# axiom_beta_plugin_module_TE0714_SATA_v0_.net
KiCad netlist of a schematic drawn in EAGLE
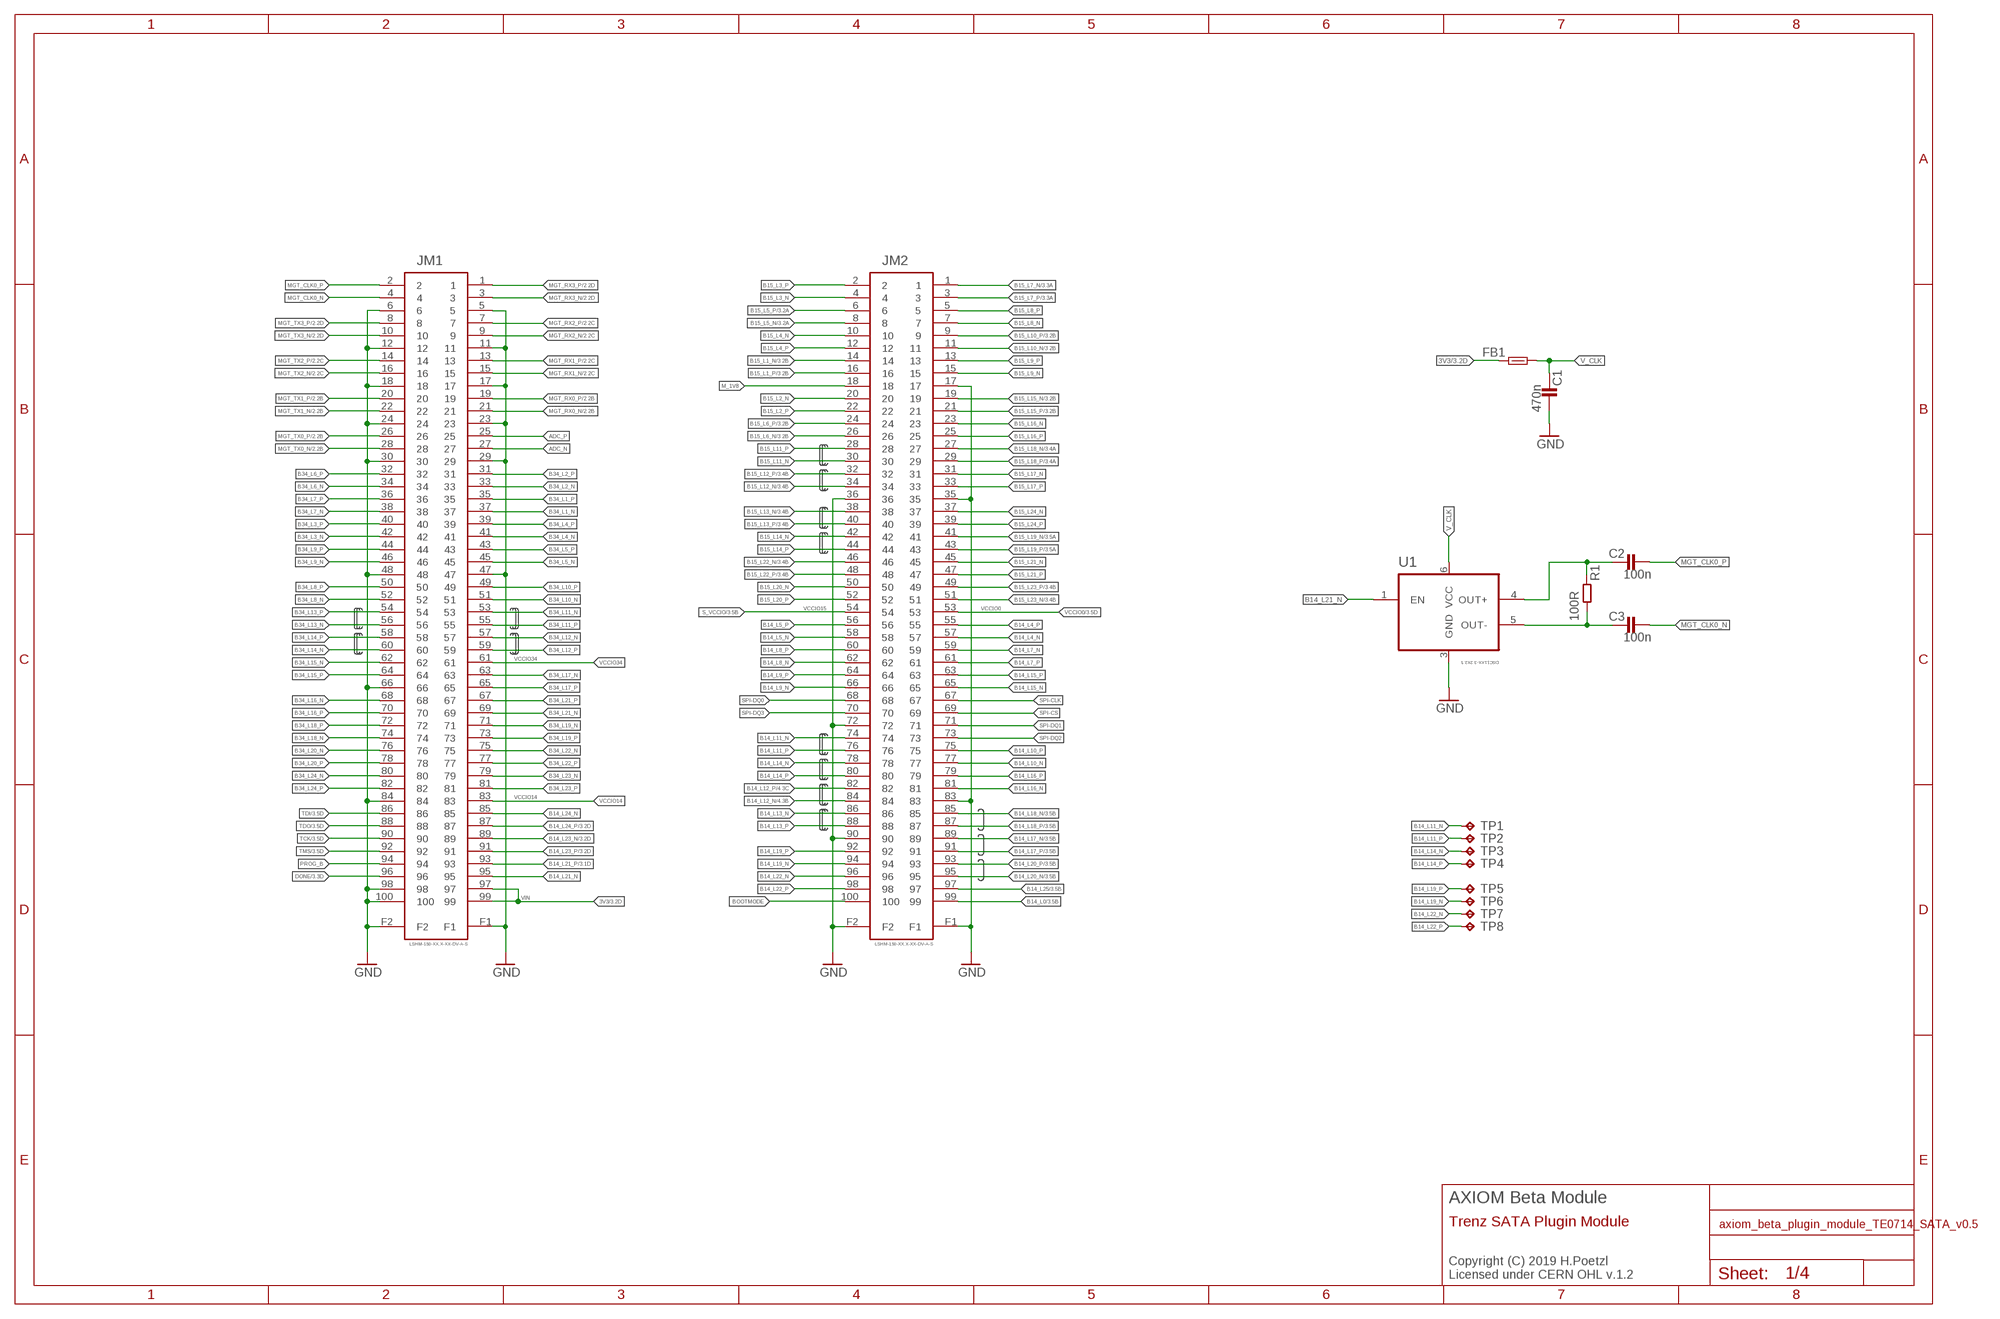
[diagram p0: schematic, sheet 1]
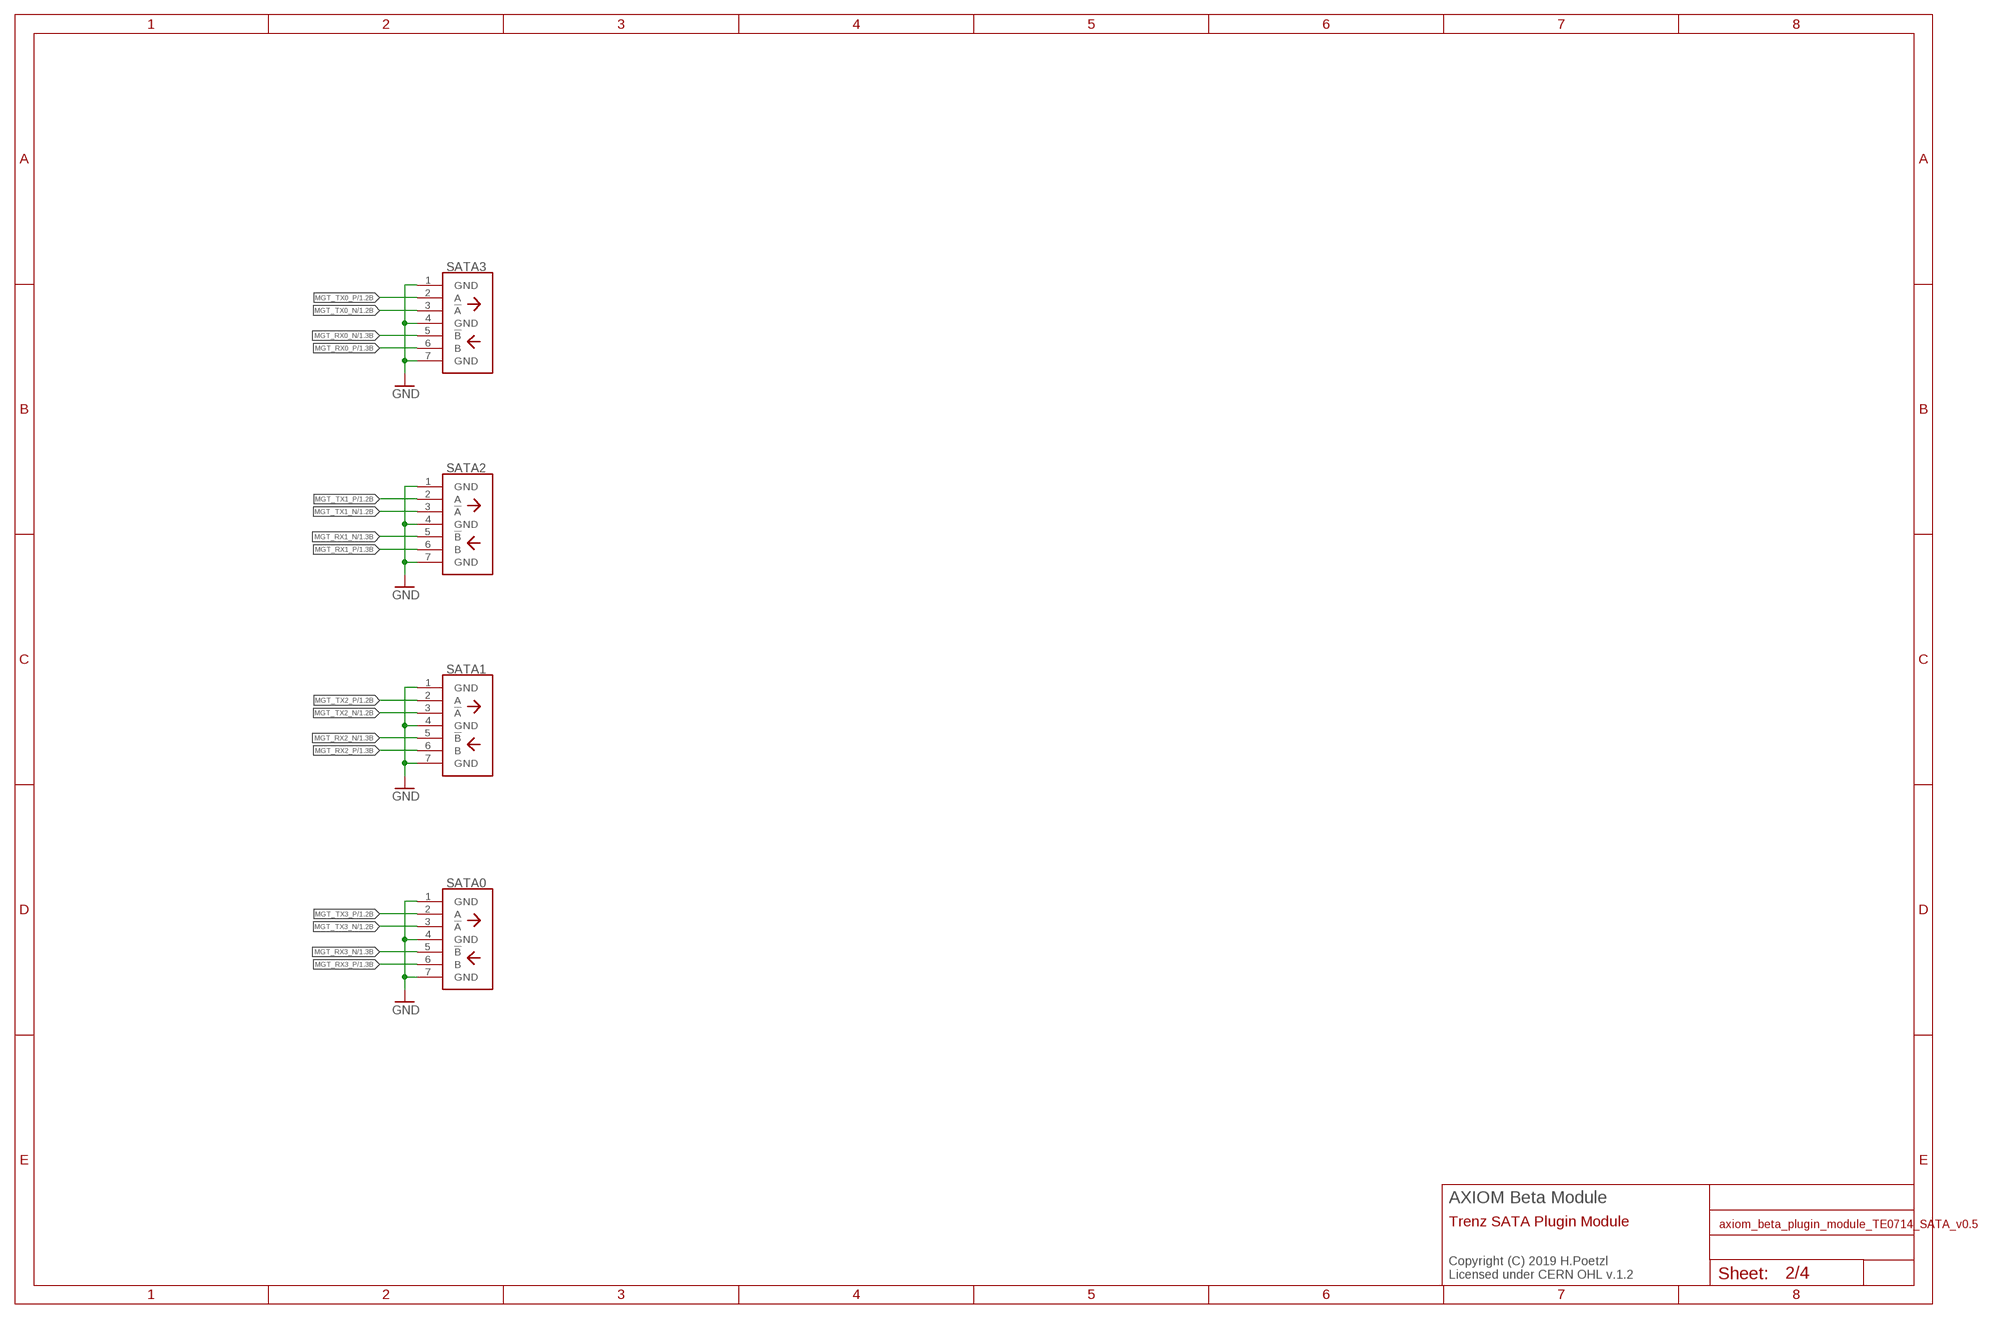
[diagram p1: schematic, sheet 2]
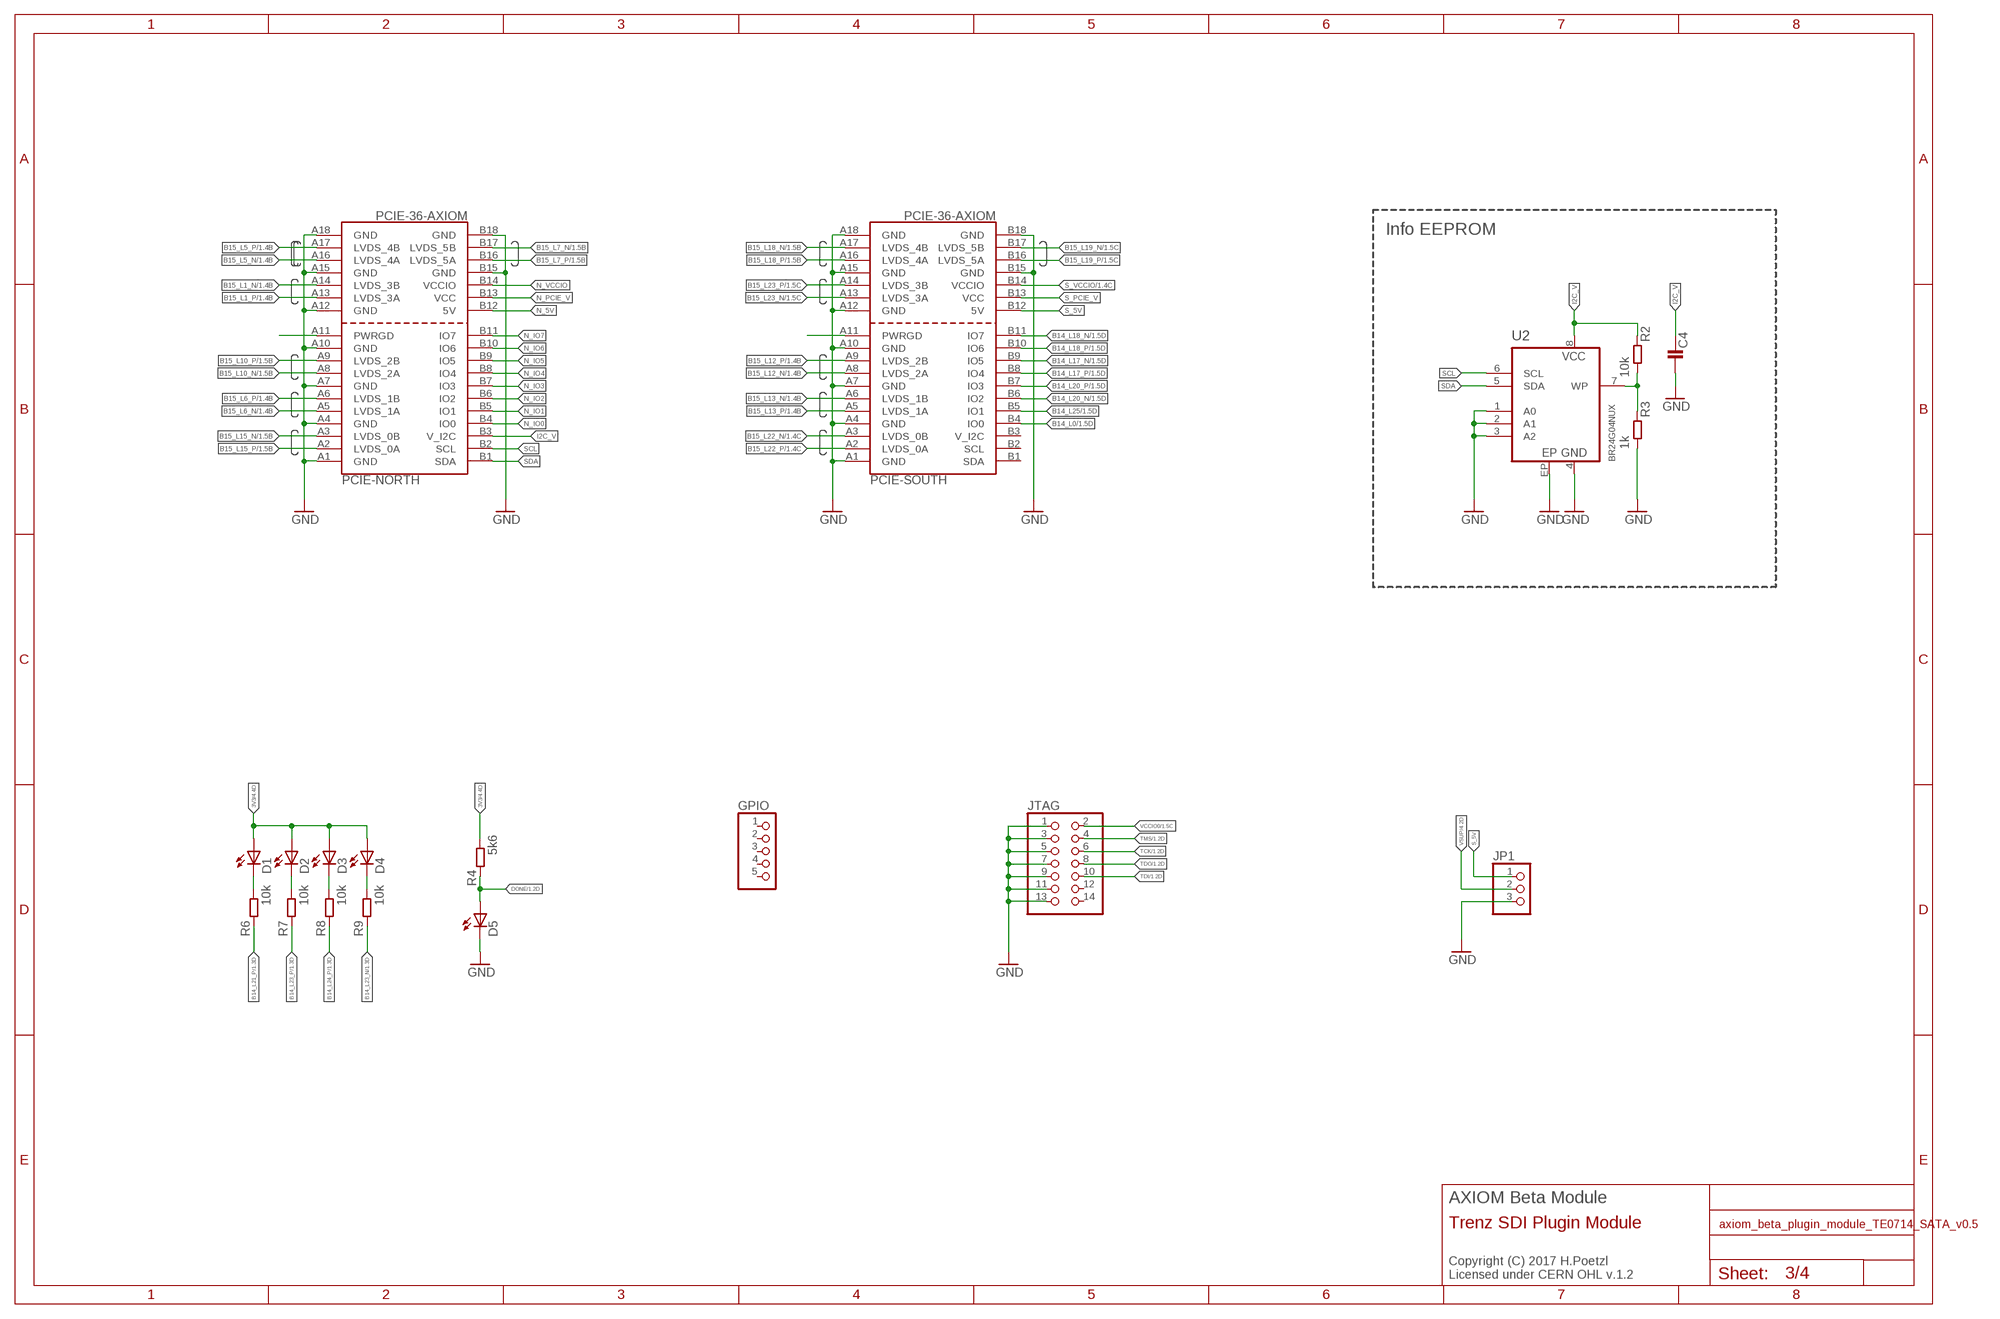
[diagram p2: schematic, sheet 3]
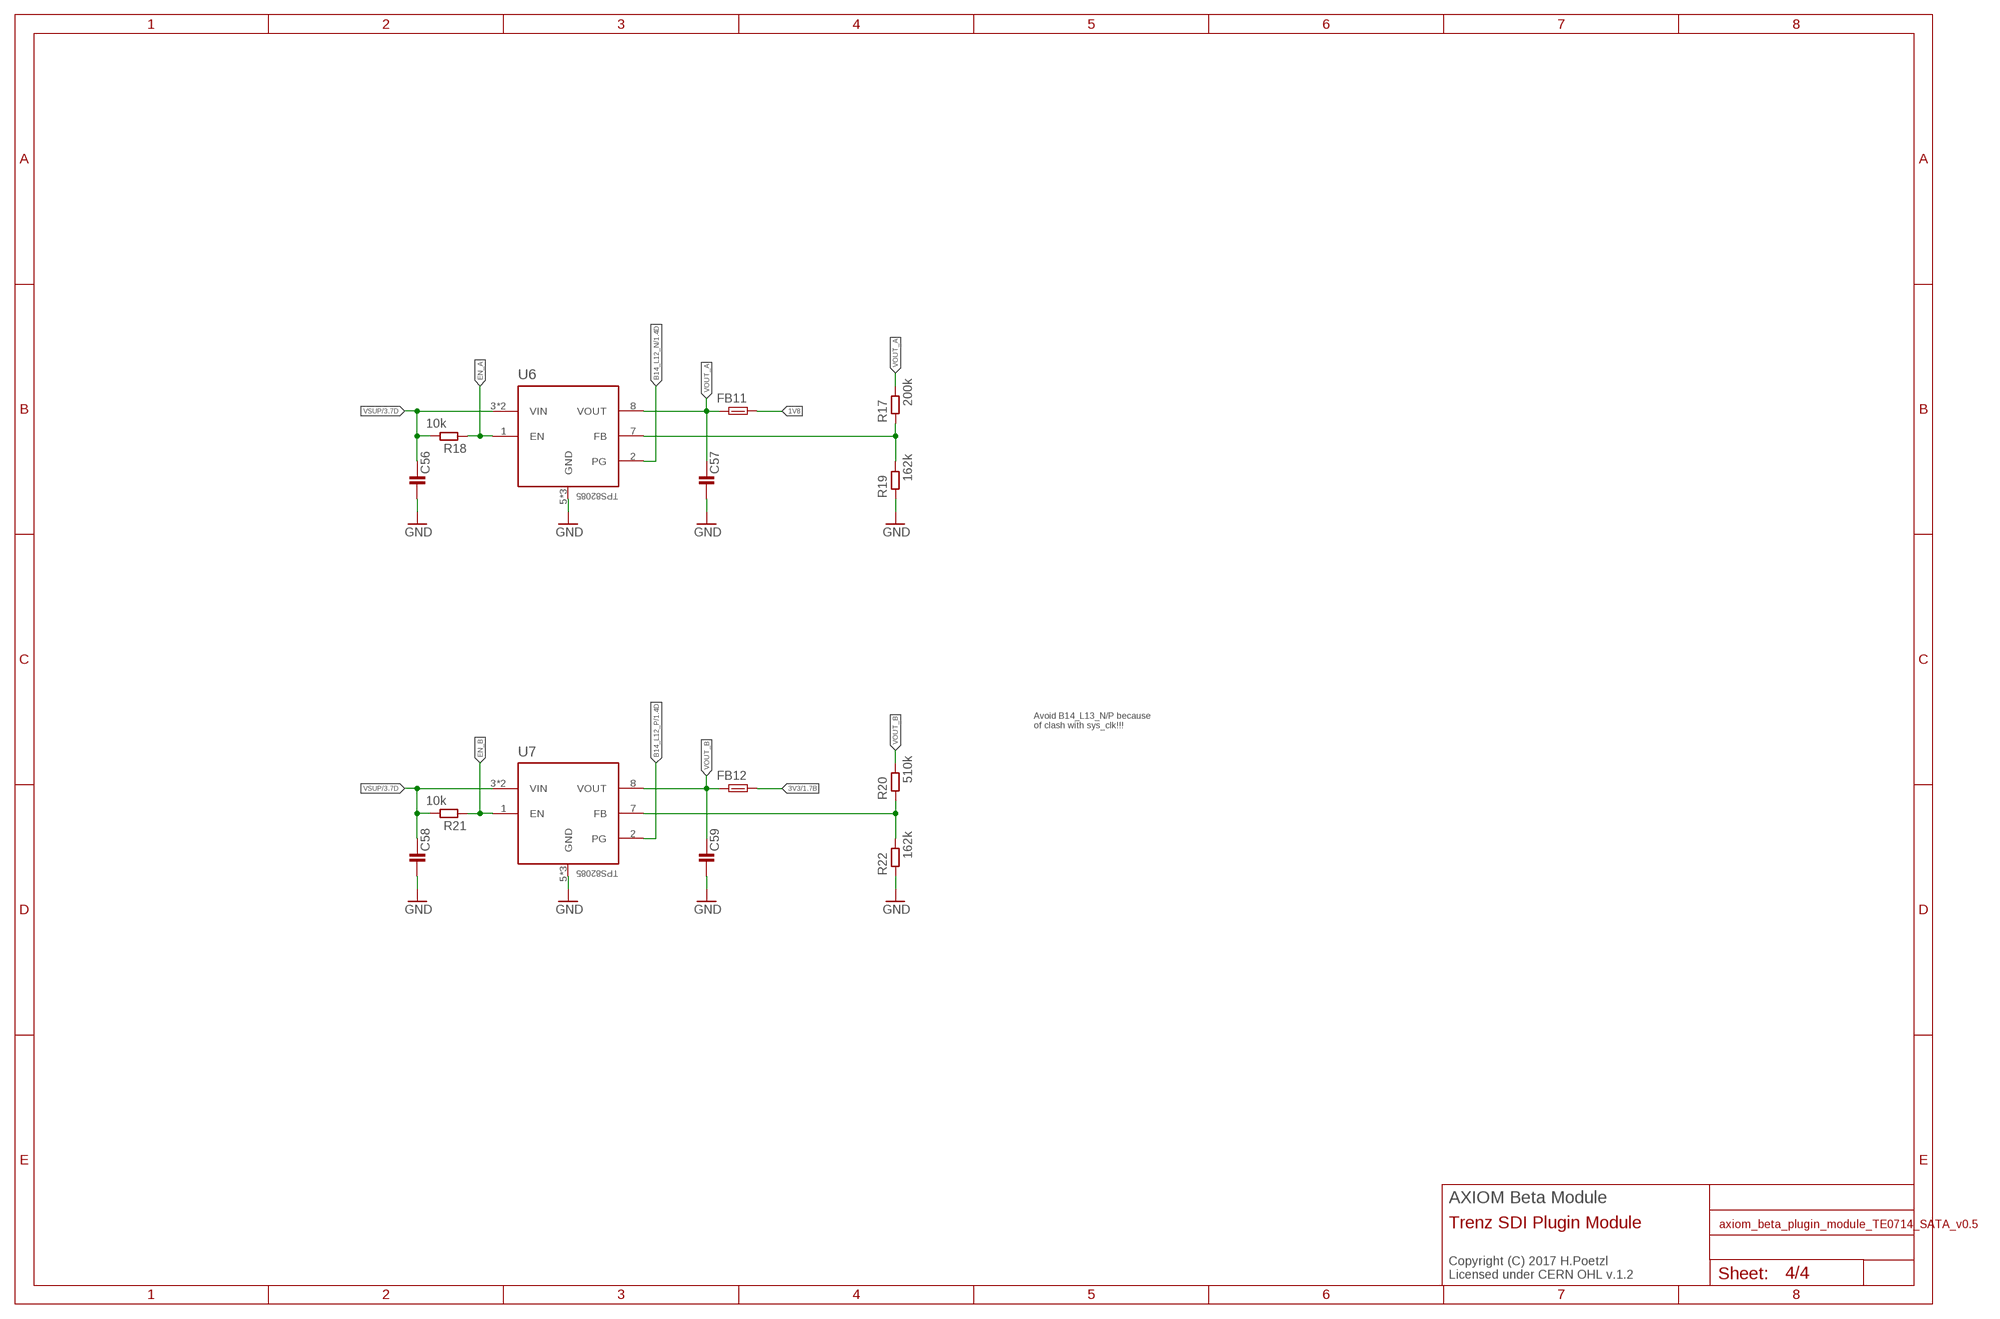
[diagram p3: schematic, sheet 4]

(export (version "E")
  (design (tool "Eeschema 10.0.6"))
  (components
    (comp (ref "C56")
      (value "C0603-C")
      (footprint "eagle-import:0603-C")
      (libsource (lib "eagle-import") (part "C0603-C"))
    )
    (comp (ref "C57")
      (value "C0603-C")
      (footprint "eagle-import:0603-C")
      (libsource (lib "eagle-import") (part "C0603-C"))
    )
    (comp (ref "C58")
      (value "C0603-C")
      (footprint "eagle-import:0603-C")
      (libsource (lib "eagle-import") (part "C0603-C"))
    )
    (comp (ref "C59")
      (value "C0603-C")
      (footprint "eagle-import:0603-C")
      (libsource (lib "eagle-import") (part "C0603-C"))
    )
    (comp (ref "FB11")
      (value "FB0603-C")
      (footprint "eagle-import:0603-C")
      (libsource (lib "eagle-import") (part "FB0603-C"))
    )
    (comp (ref "FB12")
      (value "FB0603-C")
      (footprint "eagle-import:0603-C")
      (libsource (lib "eagle-import") (part "FB0603-C"))
    )
    (comp (ref "R17")
      (value "200k")
      (footprint "eagle-import:0201-C")
      (libsource (lib "eagle-import") (part "R0201-C"))
    )
    (comp (ref "R18")
      (value "10k")
      (footprint "eagle-import:0201-C")
      (libsource (lib "eagle-import") (part "R0201-C"))
    )
    (comp (ref "R19")
      (value "162k")
      (footprint "eagle-import:0201-C")
      (libsource (lib "eagle-import") (part "R0201-C"))
    )
    (comp (ref "R20")
      (value "510k")
      (footprint "eagle-import:0201-C")
      (libsource (lib "eagle-import") (part "R0201-C"))
    )
    (comp (ref "R21")
      (value "10k")
      (footprint "eagle-import:0201-C")
      (libsource (lib "eagle-import") (part "R0201-C"))
    )
    (comp (ref "R22")
      (value "162k")
      (footprint "eagle-import:0201-C")
      (libsource (lib "eagle-import") (part "R0201-C"))
    )
    (comp (ref "U6")
      (value "TPS82085")
      (footprint "eagle-import:MICROSIP")
      (libsource (lib "eagle-import") (part "TPS82085"))
    )
    (comp (ref "U7")
      (value "TPS82085")
      (footprint "eagle-import:MICROSIP")
      (libsource (lib "eagle-import") (part "TPS82085"))
    )
    (comp (ref "C1")
      (value "470n")
      (footprint "eagle-import:0402-C")
      (libsource (lib "eagle-import") (part "C0402-C"))
    )
    (comp (ref "C2")
      (value "100n")
      (footprint "eagle-import:0201-C")
      (libsource (lib "eagle-import") (part "C0201-C"))
    )
    (comp (ref "C3")
      (value "100n")
      (footprint "eagle-import:0201-C")
      (libsource (lib "eagle-import") (part "C0201-C"))
    )
    (comp (ref "FB1")
      (value "FB0402-C")
      (footprint "eagle-import:0402-C")
      (libsource (lib "eagle-import") (part "FB0402-C"))
    )
    (comp (ref "JM1")
      (value "LSHM-150-XX.X-XX-DV-A-S")
      (footprint "eagle-import:LSHM-150-XX.X-XX-DV-A-S")
      (libsource (lib "eagle-import") (part "LSHM-150-XX.X-XX-DV-A-S"))
    )
    (comp (ref "JM2")
      (value "LSHM-150-XX.X-XX-DV-A-S")
      (footprint "eagle-import:LSHM-150-XX.X-XX-DV-A-S")
      (libsource (lib "eagle-import") (part "LSHM-150-XX.X-XX-DV-A-S"))
    )
    (comp (ref "R1")
      (value "100R")
      (footprint "eagle-import:0201-C")
      (libsource (lib "eagle-import") (part "R0201-C"))
    )
    (comp (ref "TP1")
      (value "TPTP08R")
      (footprint "eagle-import:TP08R")
      (libsource (lib "eagle-import") (part "TPTP08R"))
    )
    (comp (ref "TP2")
      (value "TPTP08R")
      (footprint "eagle-import:TP08R")
      (libsource (lib "eagle-import") (part "TPTP08R"))
    )
    (comp (ref "TP3")
      (value "TPTP08R")
      (footprint "eagle-import:TP08R")
      (libsource (lib "eagle-import") (part "TPTP08R"))
    )
    (comp (ref "TP4")
      (value "TPTP08R")
      (footprint "eagle-import:TP08R")
      (libsource (lib "eagle-import") (part "TPTP08R"))
    )
    (comp (ref "TP5")
      (value "TPTP10R")
      (footprint "eagle-import:TP10R")
      (libsource (lib "eagle-import") (part "TPTP10R"))
    )
    (comp (ref "TP6")
      (value "TPTP10R")
      (footprint "eagle-import:TP10R")
      (libsource (lib "eagle-import") (part "TPTP10R"))
    )
    (comp (ref "TP7")
      (value "TPTP10R")
      (footprint "eagle-import:TP10R")
      (libsource (lib "eagle-import") (part "TPTP10R"))
    )
    (comp (ref "TP8")
      (value "TPTP10R")
      (footprint "eagle-import:TP10R")
      (libsource (lib "eagle-import") (part "TPTP10R"))
    )
    (comp (ref "U1")
      (value "DSC11XX-3.2X2.5")
      (footprint "eagle-import:3.2X2.5")
      (libsource (lib "eagle-import") (part "DSC11XX-3.2X2.5"))
    )
    (comp (ref "SATA0")
      (value "SATA7-VERT")
      (footprint "eagle-import:SATA7-VERT")
      (libsource (lib "eagle-import") (part "SATA7-VERT"))
    )
    (comp (ref "SATA1")
      (value "SATA7-VERT")
      (footprint "eagle-import:SATA7-VERT")
      (libsource (lib "eagle-import") (part "SATA7-VERT"))
    )
    (comp (ref "SATA2")
      (value "SATA7-VERT")
      (footprint "eagle-import:SATA7-VERT")
      (libsource (lib "eagle-import") (part "SATA7-VERT"))
    )
    (comp (ref "SATA3")
      (value "SATA7-VERT")
      (footprint "eagle-import:SATA7-VERT")
      (libsource (lib "eagle-import") (part "SATA7-VERT"))
    )
    (comp (ref "C4")
      (value "C0402-B")
      (footprint "eagle-import:0402-B")
      (libsource (lib "eagle-import") (part "C0402-B"))
    )
    (comp (ref "D1")
      (value "LED")
      (footprint "eagle-import:CHIPLED_0603")
      (libsource (lib "eagle-import") (part "LED"))
    )
    (comp (ref "D2")
      (value "LED")
      (footprint "eagle-import:CHIPLED_0603")
      (libsource (lib "eagle-import") (part "LED"))
    )
    (comp (ref "D3")
      (value "LED")
      (footprint "eagle-import:CHIPLED_0603")
      (libsource (lib "eagle-import") (part "LED"))
    )
    (comp (ref "D4")
      (value "LED")
      (footprint "eagle-import:CHIPLED_0603")
      (libsource (lib "eagle-import") (part "LED"))
    )
    (comp (ref "D5")
      (value "LED")
      (footprint "eagle-import:CHIPLED_0603")
      (libsource (lib "eagle-import") (part "LED"))
    )
    (comp (ref "GPIO")
      (value "PINHD-1X05_2.00")
      (footprint "eagle-import:1X05M")
      (libsource (lib "eagle-import") (part "PINHD-1X05_2.00"))
    )
    (comp (ref "JP1")
      (value "PINHD-1X03_2.54-90°-S")
      (footprint "eagle-import:1X03_90-S")
      (libsource (lib "eagle-import") (part "PINHD-1X03_2.54-90°-S"))
    )
    (comp (ref "JTAG")
      (value "PINHD-2X07_2.00")
      (footprint "eagle-import:2X07M")
      (libsource (lib "eagle-import") (part "PINHD-2X07_2.00"))
    )
    (comp (ref "PCIE-NORTH")
      (value "PCIE-36-AXIOM")
      (footprint "eagle-import:PCIE-36-AXIOM")
      (libsource (lib "eagle-import") (part "PCIE-36-AXIOM"))
    )
    (comp (ref "PCIE-SOUTH")
      (value "PCIE-36-AXIOM")
      (footprint "eagle-import:PCIE-36-AXIOM")
      (libsource (lib "eagle-import") (part "PCIE-36-AXIOM"))
    )
    (comp (ref "R2")
      (value "10k")
      (footprint "eagle-import:0402-B")
      (libsource (lib "eagle-import") (part "R0402-B"))
    )
    (comp (ref "R3")
      (value "1k")
      (footprint "eagle-import:0402-B")
      (libsource (lib "eagle-import") (part "R0402-B"))
    )
    (comp (ref "R4")
      (value "5k6")
      (footprint "eagle-import:0402-C")
      (libsource (lib "eagle-import") (part "R0402-C"))
    )
    (comp (ref "R6")
      (value "10k")
      (footprint "eagle-import:0402-C")
      (libsource (lib "eagle-import") (part "R0402-C"))
    )
    (comp (ref "R7")
      (value "10k")
      (footprint "eagle-import:0402-C")
      (libsource (lib "eagle-import") (part "R0402-C"))
    )
    (comp (ref "R8")
      (value "10k")
      (footprint "eagle-import:0402-C")
      (libsource (lib "eagle-import") (part "R0402-C"))
    )
    (comp (ref "R9")
      (value "10k")
      (footprint "eagle-import:0402-C")
      (libsource (lib "eagle-import") (part "R0402-C"))
    )
    (comp (ref "U2")
      (value "BR24G04NUX")
      (footprint "eagle-import:DFN200X300X100-9N")
      (libsource (lib "eagle-import") (part "BR24G04NUX"))
    )
  )
  (nets
    (net (code "1") (name "1V8") (class "Default")
      (node (ref "FB11") (pin "2") (pinfunction "2_2") (pintype "passive"))
    )
    (net (code "2") (name "3V3") (class "Default")
      (node (ref "D1") (pin "A") (pinfunction "A_A") (pintype "passive"))
      (node (ref "D2") (pin "A") (pinfunction "A_A") (pintype "passive"))
      (node (ref "D3") (pin "A") (pinfunction "A_A") (pintype "passive"))
      (node (ref "D4") (pin "A") (pinfunction "A_A") (pintype "passive"))
      (node (ref "FB1") (pin "1") (pinfunction "1_1") (pintype "passive"))
      (node (ref "FB12") (pin "2") (pinfunction "2_2") (pintype "passive"))
      (node (ref "JM1") (pin "97") (pinfunction "97_97") (pintype "bidirectional"))
      (node (ref "JM1") (pin "99") (pinfunction "99_99") (pintype "bidirectional"))
      (node (ref "R4") (pin "2") (pinfunction "2_2") (pintype "passive"))
    )
    (net (code "3") (name "ADC_N") (class "Default")
      (node (ref "JM1") (pin "27") (pinfunction "27_27") (pintype "bidirectional"))
    )
    (net (code "4") (name "ADC_P") (class "Default")
      (node (ref "JM1") (pin "25") (pinfunction "25_25") (pintype "bidirectional"))
    )
    (net (code "5") (name "B14_L0") (class "Default")
      (node (ref "JM2") (pin "99") (pinfunction "99_99") (pintype "bidirectional"))
      (node (ref "PCIE-SOUTH") (pin "B4") (pinfunction "IO0_B4") (pintype "passive"))
    )
    (net (code "6") (name "B14_L4_N") (class "Default")
      (node (ref "JM2") (pin "57") (pinfunction "57_57") (pintype "bidirectional"))
    )
    (net (code "7") (name "B14_L4_P") (class "Default")
      (node (ref "JM2") (pin "55") (pinfunction "55_55") (pintype "bidirectional"))
    )
    (net (code "8") (name "B14_L5_N") (class "Default")
      (node (ref "JM2") (pin "58") (pinfunction "58_58") (pintype "bidirectional"))
    )
    (net (code "9") (name "B14_L5_P") (class "Default")
      (node (ref "JM2") (pin "56") (pinfunction "56_56") (pintype "bidirectional"))
    )
    (net (code "10") (name "B14_L7_N") (class "Default")
      (node (ref "JM2") (pin "59") (pinfunction "59_59") (pintype "bidirectional"))
    )
    (net (code "11") (name "B14_L7_P") (class "Default")
      (node (ref "JM2") (pin "61") (pinfunction "61_61") (pintype "bidirectional"))
    )
    (net (code "12") (name "B14_L8_N") (class "Default")
      (node (ref "JM2") (pin "62") (pinfunction "62_62") (pintype "bidirectional"))
    )
    (net (code "13") (name "B14_L8_P") (class "Default")
      (node (ref "JM2") (pin "60") (pinfunction "60_60") (pintype "bidirectional"))
    )
    (net (code "14") (name "B14_L9_N") (class "Default")
      (node (ref "JM2") (pin "66") (pinfunction "66_66") (pintype "bidirectional"))
    )
    (net (code "15") (name "B14_L9_P") (class "Default")
      (node (ref "JM2") (pin "64") (pinfunction "64_64") (pintype "bidirectional"))
    )
    (net (code "16") (name "B14_L10_N") (class "Default")
      (node (ref "JM2") (pin "77") (pinfunction "77_77") (pintype "bidirectional"))
    )
    (net (code "17") (name "B14_L10_P") (class "Default")
      (node (ref "JM2") (pin "75") (pinfunction "75_75") (pintype "bidirectional"))
    )
    (net (code "18") (name "B14_L11_N") (class "Default")
      (node (ref "JM2") (pin "74") (pinfunction "74_74") (pintype "bidirectional"))
      (node (ref "TP1") (pin "TP") (pinfunction "TP_TP") (pintype "input"))
    )
    (net (code "19") (name "B14_L11_P") (class "Default")
      (node (ref "JM2") (pin "76") (pinfunction "76_76") (pintype "bidirectional"))
      (node (ref "TP2") (pin "TP") (pinfunction "TP_TP") (pintype "input"))
    )
    (net (code "20") (name "B14_L12_N") (class "Default")
      (node (ref "JM2") (pin "84") (pinfunction "84_84") (pintype "bidirectional"))
      (node (ref "U6") (pin "2") (pinfunction "PG_2") (pintype "power_in"))
    )
    (net (code "21") (name "B14_L12_P") (class "Default")
      (node (ref "JM2") (pin "82") (pinfunction "82_82") (pintype "bidirectional"))
      (node (ref "U7") (pin "2") (pinfunction "PG_2") (pintype "power_in"))
    )
    (net (code "22") (name "B14_L13_N") (class "Default")
      (node (ref "JM2") (pin "86") (pinfunction "86_86") (pintype "bidirectional"))
    )
    (net (code "23") (name "B14_L13_P") (class "Default")
      (node (ref "JM2") (pin "88") (pinfunction "88_88") (pintype "bidirectional"))
    )
    (net (code "24") (name "B14_L14_N") (class "Default")
      (node (ref "JM2") (pin "78") (pinfunction "78_78") (pintype "bidirectional"))
      (node (ref "TP3") (pin "TP") (pinfunction "TP_TP") (pintype "input"))
    )
    (net (code "25") (name "B14_L14_P") (class "Default")
      (node (ref "JM2") (pin "80") (pinfunction "80_80") (pintype "bidirectional"))
      (node (ref "TP4") (pin "TP") (pinfunction "TP_TP") (pintype "input"))
    )
    (net (code "26") (name "B14_L15_N") (class "Default")
      (node (ref "JM2") (pin "65") (pinfunction "65_65") (pintype "bidirectional"))
    )
    (net (code "27") (name "B14_L15_P") (class "Default")
      (node (ref "JM2") (pin "63") (pinfunction "63_63") (pintype "bidirectional"))
    )
    (net (code "28") (name "B14_L16_N") (class "Default")
      (node (ref "JM2") (pin "81") (pinfunction "81_81") (pintype "bidirectional"))
    )
    (net (code "29") (name "B14_L16_P") (class "Default")
      (node (ref "JM2") (pin "79") (pinfunction "79_79") (pintype "bidirectional"))
    )
    (net (code "30") (name "B14_L17_N") (class "Default")
      (node (ref "JM2") (pin "89") (pinfunction "89_89") (pintype "bidirectional"))
      (node (ref "PCIE-SOUTH") (pin "B9") (pinfunction "IO5_B9") (pintype "passive"))
    )
    (net (code "31") (name "B14_L17_P") (class "Default")
      (node (ref "JM2") (pin "91") (pinfunction "91_91") (pintype "bidirectional"))
      (node (ref "PCIE-SOUTH") (pin "B8") (pinfunction "IO4_B8") (pintype "passive"))
    )
    (net (code "32") (name "B14_L18_N") (class "Default")
      (node (ref "JM2") (pin "85") (pinfunction "85_85") (pintype "bidirectional"))
      (node (ref "PCIE-SOUTH") (pin "B11") (pinfunction "IO7_B11") (pintype "passive"))
    )
    (net (code "33") (name "B14_L18_P") (class "Default")
      (node (ref "JM2") (pin "87") (pinfunction "87_87") (pintype "bidirectional"))
      (node (ref "PCIE-SOUTH") (pin "B10") (pinfunction "IO6_B10") (pintype "passive"))
    )
    (net (code "34") (name "B14_L19_N") (class "Default")
      (node (ref "JM2") (pin "94") (pinfunction "94_94") (pintype "bidirectional"))
      (node (ref "TP6") (pin "TP") (pinfunction "TP_TP") (pintype "input"))
    )
    (net (code "35") (name "B14_L19_P") (class "Default")
      (node (ref "JM2") (pin "92") (pinfunction "92_92") (pintype "bidirectional"))
      (node (ref "TP5") (pin "TP") (pinfunction "TP_TP") (pintype "input"))
    )
    (net (code "36") (name "B14_L20_N") (class "Default")
      (node (ref "JM2") (pin "95") (pinfunction "95_95") (pintype "bidirectional"))
      (node (ref "PCIE-SOUTH") (pin "B6") (pinfunction "IO2_B6") (pintype "passive"))
    )
    (net (code "37") (name "B14_L20_P") (class "Default")
      (node (ref "JM2") (pin "93") (pinfunction "93_93") (pintype "bidirectional"))
      (node (ref "PCIE-SOUTH") (pin "B7") (pinfunction "IO3_B7") (pintype "passive"))
    )
    (net (code "38") (name "B14_L21_N") (class "Default")
      (node (ref "JM1") (pin "95") (pinfunction "95_95") (pintype "bidirectional"))
      (node (ref "U1") (pin "1") (pinfunction "EN_1") (pintype "input"))
    )
    (net (code "39") (name "B14_L21_P") (class "Default")
      (node (ref "JM1") (pin "93") (pinfunction "93_93") (pintype "bidirectional"))
      (node (ref "R6") (pin "1") (pinfunction "1_1") (pintype "passive"))
    )
    (net (code "40") (name "B14_L22_N") (class "Default")
      (node (ref "JM2") (pin "96") (pinfunction "96_96") (pintype "bidirectional"))
      (node (ref "TP7") (pin "TP") (pinfunction "TP_TP") (pintype "input"))
    )
    (net (code "41") (name "B14_L22_P") (class "Default")
      (node (ref "JM2") (pin "98") (pinfunction "98_98") (pintype "bidirectional"))
      (node (ref "TP8") (pin "TP") (pinfunction "TP_TP") (pintype "input"))
    )
    (net (code "42") (name "B14_L23_N") (class "Default")
      (node (ref "JM1") (pin "89") (pinfunction "89_89") (pintype "bidirectional"))
      (node (ref "R9") (pin "1") (pinfunction "1_1") (pintype "passive"))
    )
    (net (code "43") (name "B14_L23_P") (class "Default")
      (node (ref "JM1") (pin "91") (pinfunction "91_91") (pintype "bidirectional"))
      (node (ref "R7") (pin "1") (pinfunction "1_1") (pintype "passive"))
    )
    (net (code "44") (name "B14_L24_N") (class "Default")
      (node (ref "JM1") (pin "85") (pinfunction "85_85") (pintype "bidirectional"))
    )
    (net (code "45") (name "B14_L24_P") (class "Default")
      (node (ref "JM1") (pin "87") (pinfunction "87_87") (pintype "bidirectional"))
      (node (ref "R8") (pin "1") (pinfunction "1_1") (pintype "passive"))
    )
    (net (code "46") (name "B14_L25") (class "Default")
      (node (ref "JM2") (pin "97") (pinfunction "97_97") (pintype "bidirectional"))
      (node (ref "PCIE-SOUTH") (pin "B5") (pinfunction "IO1_B5") (pintype "passive"))
    )
    (net (code "47") (name "B15_L1_N") (class "Default")
      (node (ref "JM2") (pin "14") (pinfunction "14_14") (pintype "bidirectional"))
      (node (ref "PCIE-NORTH") (pin "A14") (pinfunction "LVDS_3B_A14") (pintype "passive"))
    )
    (net (code "48") (name "B15_L1_P") (class "Default")
      (node (ref "JM2") (pin "16") (pinfunction "16_16") (pintype "bidirectional"))
      (node (ref "PCIE-NORTH") (pin "A13") (pinfunction "LVDS_3A_A13") (pintype "passive"))
    )
    (net (code "49") (name "B15_L2_N") (class "Default")
      (node (ref "JM2") (pin "20") (pinfunction "20_20") (pintype "bidirectional"))
    )
    (net (code "50") (name "B15_L2_P") (class "Default")
      (node (ref "JM2") (pin "22") (pinfunction "22_22") (pintype "bidirectional"))
    )
    (net (code "51") (name "B15_L3_N") (class "Default")
      (node (ref "JM2") (pin "4") (pinfunction "4_4") (pintype "bidirectional"))
    )
    (net (code "52") (name "B15_L3_P") (class "Default")
      (node (ref "JM2") (pin "2") (pinfunction "2_2") (pintype "bidirectional"))
    )
    (net (code "53") (name "B15_L4_N") (class "Default")
      (node (ref "JM2") (pin "10") (pinfunction "10_10") (pintype "bidirectional"))
    )
    (net (code "54") (name "B15_L4_P") (class "Default")
      (node (ref "JM2") (pin "12") (pinfunction "12_12") (pintype "bidirectional"))
    )
    (net (code "55") (name "B15_L5_N") (class "Default")
      (node (ref "JM2") (pin "8") (pinfunction "8_8") (pintype "bidirectional"))
      (node (ref "PCIE-NORTH") (pin "A16") (pinfunction "LVDS_4A_A16") (pintype "passive"))
    )
    (net (code "56") (name "B15_L5_P") (class "Default")
      (node (ref "JM2") (pin "6") (pinfunction "6_6") (pintype "bidirectional"))
      (node (ref "PCIE-NORTH") (pin "A17") (pinfunction "LVDS_4B_A17") (pintype "passive"))
    )
    (net (code "57") (name "B15_L6_N") (class "Default")
      (node (ref "JM2") (pin "26") (pinfunction "26_26") (pintype "bidirectional"))
      (node (ref "PCIE-NORTH") (pin "A5") (pinfunction "LVDS_1A_A5") (pintype "passive"))
    )
    (net (code "58") (name "B15_L6_P") (class "Default")
      (node (ref "JM2") (pin "24") (pinfunction "24_24") (pintype "bidirectional"))
      (node (ref "PCIE-NORTH") (pin "A6") (pinfunction "LVDS_1B_A6") (pintype "passive"))
    )
    (net (code "59") (name "B15_L7_N") (class "Default")
      (node (ref "JM2") (pin "1") (pinfunction "1_1") (pintype "bidirectional"))
      (node (ref "PCIE-NORTH") (pin "B17") (pinfunction "LVDS_5B_B17") (pintype "passive"))
    )
    (net (code "60") (name "B15_L7_P") (class "Default")
      (node (ref "JM2") (pin "3") (pinfunction "3_3") (pintype "bidirectional"))
      (node (ref "PCIE-NORTH") (pin "B16") (pinfunction "LVDS_5A_B16") (pintype "passive"))
    )
    (net (code "61") (name "B15_L8_N") (class "Default")
      (node (ref "JM2") (pin "7") (pinfunction "7_7") (pintype "bidirectional"))
    )
    (net (code "62") (name "B15_L8_P") (class "Default")
      (node (ref "JM2") (pin "5") (pinfunction "5_5") (pintype "bidirectional"))
    )
    (net (code "63") (name "B15_L9_N") (class "Default")
      (node (ref "JM2") (pin "15") (pinfunction "15_15") (pintype "bidirectional"))
    )
    (net (code "64") (name "B15_L9_P") (class "Default")
      (node (ref "JM2") (pin "13") (pinfunction "13_13") (pintype "bidirectional"))
    )
    (net (code "65") (name "B15_L10_N") (class "Default")
      (node (ref "JM2") (pin "11") (pinfunction "11_11") (pintype "bidirectional"))
      (node (ref "PCIE-NORTH") (pin "A8") (pinfunction "LVDS_2A_A8") (pintype "passive"))
    )
    (net (code "66") (name "B15_L10_P") (class "Default")
      (node (ref "JM2") (pin "9") (pinfunction "9_9") (pintype "bidirectional"))
      (node (ref "PCIE-NORTH") (pin "A9") (pinfunction "LVDS_2B_A9") (pintype "passive"))
    )
    (net (code "67") (name "B15_L11_N") (class "Default")
      (node (ref "JM2") (pin "30") (pinfunction "30_30") (pintype "bidirectional"))
    )
    (net (code "68") (name "B15_L11_P") (class "Default")
      (node (ref "JM2") (pin "28") (pinfunction "28_28") (pintype "bidirectional"))
    )
    (net (code "69") (name "B15_L12_N") (class "Default")
      (node (ref "JM2") (pin "34") (pinfunction "34_34") (pintype "bidirectional"))
      (node (ref "PCIE-SOUTH") (pin "A8") (pinfunction "LVDS_2A_A8") (pintype "passive"))
    )
    (net (code "70") (name "B15_L12_P") (class "Default")
      (node (ref "JM2") (pin "32") (pinfunction "32_32") (pintype "bidirectional"))
      (node (ref "PCIE-SOUTH") (pin "A9") (pinfunction "LVDS_2B_A9") (pintype "passive"))
    )
    (net (code "71") (name "B15_L13_N") (class "Default")
      (node (ref "JM2") (pin "38") (pinfunction "38_38") (pintype "bidirectional"))
      (node (ref "PCIE-SOUTH") (pin "A6") (pinfunction "LVDS_1B_A6") (pintype "passive"))
    )
    (net (code "72") (name "B15_L13_P") (class "Default")
      (node (ref "JM2") (pin "40") (pinfunction "40_40") (pintype "bidirectional"))
      (node (ref "PCIE-SOUTH") (pin "A5") (pinfunction "LVDS_1A_A5") (pintype "passive"))
    )
    (net (code "73") (name "B15_L14_N") (class "Default")
      (node (ref "JM2") (pin "42") (pinfunction "42_42") (pintype "bidirectional"))
    )
    (net (code "74") (name "B15_L14_P") (class "Default")
      (node (ref "JM2") (pin "44") (pinfunction "44_44") (pintype "bidirectional"))
    )
    (net (code "75") (name "B15_L15_N") (class "Default")
      (node (ref "JM2") (pin "19") (pinfunction "19_19") (pintype "bidirectional"))
      (node (ref "PCIE-NORTH") (pin "A3") (pinfunction "LVDS_0B_A3") (pintype "passive"))
    )
    (net (code "76") (name "B15_L15_P") (class "Default")
      (node (ref "JM2") (pin "21") (pinfunction "21_21") (pintype "bidirectional"))
      (node (ref "PCIE-NORTH") (pin "A2") (pinfunction "LVDS_0A_A2") (pintype "passive"))
    )
    (net (code "77") (name "B15_L16_N") (class "Default")
      (node (ref "JM2") (pin "23") (pinfunction "23_23") (pintype "bidirectional"))
    )
    (net (code "78") (name "B15_L16_P") (class "Default")
      (node (ref "JM2") (pin "25") (pinfunction "25_25") (pintype "bidirectional"))
    )
    (net (code "79") (name "B15_L17_N") (class "Default")
      (node (ref "JM2") (pin "31") (pinfunction "31_31") (pintype "bidirectional"))
    )
    (net (code "80") (name "B15_L17_P") (class "Default")
      (node (ref "JM2") (pin "33") (pinfunction "33_33") (pintype "bidirectional"))
    )
    (net (code "81") (name "B15_L18_N") (class "Default")
      (node (ref "JM2") (pin "27") (pinfunction "27_27") (pintype "bidirectional"))
      (node (ref "PCIE-SOUTH") (pin "A17") (pinfunction "LVDS_4B_A17") (pintype "passive"))
    )
    (net (code "82") (name "B15_L18_P") (class "Default")
      (node (ref "JM2") (pin "29") (pinfunction "29_29") (pintype "bidirectional"))
      (node (ref "PCIE-SOUTH") (pin "A16") (pinfunction "LVDS_4A_A16") (pintype "passive"))
    )
    (net (code "83") (name "B15_L19_N") (class "Default")
      (node (ref "JM2") (pin "41") (pinfunction "41_41") (pintype "bidirectional"))
      (node (ref "PCIE-SOUTH") (pin "B17") (pinfunction "LVDS_5B_B17") (pintype "passive"))
    )
    (net (code "84") (name "B15_L19_P") (class "Default")
      (node (ref "JM2") (pin "43") (pinfunction "43_43") (pintype "bidirectional"))
      (node (ref "PCIE-SOUTH") (pin "B16") (pinfunction "LVDS_5A_B16") (pintype "passive"))
    )
    (net (code "85") (name "B15_L20_N") (class "Default")
      (node (ref "JM2") (pin "50") (pinfunction "50_50") (pintype "bidirectional"))
    )
    (net (code "86") (name "B15_L20_P") (class "Default")
      (node (ref "JM2") (pin "52") (pinfunction "52_52") (pintype "bidirectional"))
    )
    (net (code "87") (name "B15_L21_N") (class "Default")
      (node (ref "JM2") (pin "45") (pinfunction "45_45") (pintype "bidirectional"))
    )
    (net (code "88") (name "B15_L21_P") (class "Default")
      (node (ref "JM2") (pin "47") (pinfunction "47_47") (pintype "bidirectional"))
    )
    (net (code "89") (name "B15_L22_N") (class "Default")
      (node (ref "JM2") (pin "46") (pinfunction "46_46") (pintype "bidirectional"))
      (node (ref "PCIE-SOUTH") (pin "A3") (pinfunction "LVDS_0B_A3") (pintype "passive"))
    )
    (net (code "90") (name "B15_L22_P") (class "Default")
      (node (ref "JM2") (pin "48") (pinfunction "48_48") (pintype "bidirectional"))
      (node (ref "PCIE-SOUTH") (pin "A2") (pinfunction "LVDS_0A_A2") (pintype "passive"))
    )
    (net (code "91") (name "B15_L23_N") (class "Default")
      (node (ref "JM2") (pin "51") (pinfunction "51_51") (pintype "bidirectional"))
      (node (ref "PCIE-SOUTH") (pin "A13") (pinfunction "LVDS_3A_A13") (pintype "passive"))
    )
    (net (code "92") (name "B15_L23_P") (class "Default")
      (node (ref "JM2") (pin "49") (pinfunction "49_49") (pintype "bidirectional"))
      (node (ref "PCIE-SOUTH") (pin "A14") (pinfunction "LVDS_3B_A14") (pintype "passive"))
    )
    (net (code "93") (name "B15_L24_N") (class "Default")
      (node (ref "JM2") (pin "37") (pinfunction "37_37") (pintype "bidirectional"))
    )
    (net (code "94") (name "B15_L24_P") (class "Default")
      (node (ref "JM2") (pin "39") (pinfunction "39_39") (pintype "bidirectional"))
    )
    (net (code "95") (name "B34_L1_N") (class "Default")
      (node (ref "JM1") (pin "37") (pinfunction "37_37") (pintype "bidirectional"))
    )
    (net (code "96") (name "B34_L1_P") (class "Default")
      (node (ref "JM1") (pin "35") (pinfunction "35_35") (pintype "bidirectional"))
    )
    (net (code "97") (name "B34_L2_N") (class "Default")
      (node (ref "JM1") (pin "33") (pinfunction "33_33") (pintype "bidirectional"))
    )
    (net (code "98") (name "B34_L2_P") (class "Default")
      (node (ref "JM1") (pin "31") (pinfunction "31_31") (pintype "bidirectional"))
    )
    (net (code "99") (name "B34_L3_N") (class "Default")
      (node (ref "JM1") (pin "42") (pinfunction "42_42") (pintype "bidirectional"))
    )
    (net (code "100") (name "B34_L3_P") (class "Default")
      (node (ref "JM1") (pin "40") (pinfunction "40_40") (pintype "bidirectional"))
    )
    (net (code "101") (name "B34_L4_N") (class "Default")
      (node (ref "JM1") (pin "41") (pinfunction "41_41") (pintype "bidirectional"))
    )
    (net (code "102") (name "B34_L4_P") (class "Default")
      (node (ref "JM1") (pin "39") (pinfunction "39_39") (pintype "bidirectional"))
    )
    (net (code "103") (name "B34_L5_N") (class "Default")
      (node (ref "JM1") (pin "45") (pinfunction "45_45") (pintype "bidirectional"))
    )
    (net (code "104") (name "B34_L5_P") (class "Default")
      (node (ref "JM1") (pin "43") (pinfunction "43_43") (pintype "bidirectional"))
    )
    (net (code "105") (name "B34_L6_N") (class "Default")
      (node (ref "JM1") (pin "34") (pinfunction "34_34") (pintype "bidirectional"))
    )
    (net (code "106") (name "B34_L6_P") (class "Default")
      (node (ref "JM1") (pin "32") (pinfunction "32_32") (pintype "bidirectional"))
    )
    (net (code "107") (name "B34_L7_N") (class "Default")
      (node (ref "JM1") (pin "38") (pinfunction "38_38") (pintype "bidirectional"))
    )
    (net (code "108") (name "B34_L7_P") (class "Default")
      (node (ref "JM1") (pin "36") (pinfunction "36_36") (pintype "bidirectional"))
    )
    (net (code "109") (name "B34_L8_N") (class "Default")
      (node (ref "JM1") (pin "52") (pinfunction "52_52") (pintype "bidirectional"))
    )
    (net (code "110") (name "B34_L8_P") (class "Default")
      (node (ref "JM1") (pin "50") (pinfunction "50_50") (pintype "bidirectional"))
    )
    (net (code "111") (name "B34_L9_N") (class "Default")
      (node (ref "JM1") (pin "46") (pinfunction "46_46") (pintype "bidirectional"))
    )
    (net (code "112") (name "B34_L9_P") (class "Default")
      (node (ref "JM1") (pin "44") (pinfunction "44_44") (pintype "bidirectional"))
    )
    (net (code "113") (name "B34_L10_N") (class "Default")
      (node (ref "JM1") (pin "51") (pinfunction "51_51") (pintype "bidirectional"))
    )
    (net (code "114") (name "B34_L10_P") (class "Default")
      (node (ref "JM1") (pin "49") (pinfunction "49_49") (pintype "bidirectional"))
    )
    (net (code "115") (name "B34_L11_N") (class "Default")
      (node (ref "JM1") (pin "53") (pinfunction "53_53") (pintype "bidirectional"))
    )
    (net (code "116") (name "B34_L11_P") (class "Default")
      (node (ref "JM1") (pin "55") (pinfunction "55_55") (pintype "bidirectional"))
    )
    (net (code "117") (name "B34_L12_N") (class "Default")
      (node (ref "JM1") (pin "57") (pinfunction "57_57") (pintype "bidirectional"))
    )
    (net (code "118") (name "B34_L12_P") (class "Default")
      (node (ref "JM1") (pin "59") (pinfunction "59_59") (pintype "bidirectional"))
    )
    (net (code "119") (name "B34_L13_N") (class "Default")
      (node (ref "JM1") (pin "56") (pinfunction "56_56") (pintype "bidirectional"))
    )
    (net (code "120") (name "B34_L13_P") (class "Default")
      (node (ref "JM1") (pin "54") (pinfunction "54_54") (pintype "bidirectional"))
    )
    (net (code "121") (name "B34_L14_N") (class "Default")
      (node (ref "JM1") (pin "60") (pinfunction "60_60") (pintype "bidirectional"))
    )
    (net (code "122") (name "B34_L14_P") (class "Default")
      (node (ref "JM1") (pin "58") (pinfunction "58_58") (pintype "bidirectional"))
    )
    (net (code "123") (name "B34_L15_N") (class "Default")
      (node (ref "JM1") (pin "62") (pinfunction "62_62") (pintype "bidirectional"))
    )
    (net (code "124") (name "B34_L15_P") (class "Default")
      (node (ref "JM1") (pin "64") (pinfunction "64_64") (pintype "bidirectional"))
    )
    (net (code "125") (name "B34_L16_N") (class "Default")
      (node (ref "JM1") (pin "68") (pinfunction "68_68") (pintype "bidirectional"))
    )
    (net (code "126") (name "B34_L16_P") (class "Default")
      (node (ref "JM1") (pin "70") (pinfunction "70_70") (pintype "bidirectional"))
    )
    (net (code "127") (name "B34_L17_N") (class "Default")
      (node (ref "JM1") (pin "63") (pinfunction "63_63") (pintype "bidirectional"))
    )
    (net (code "128") (name "B34_L17_P") (class "Default")
      (node (ref "JM1") (pin "65") (pinfunction "65_65") (pintype "bidirectional"))
    )
    (net (code "129") (name "B34_L18_N") (class "Default")
      (node (ref "JM1") (pin "74") (pinfunction "74_74") (pintype "bidirectional"))
    )
    (net (code "130") (name "B34_L18_P") (class "Default")
      (node (ref "JM1") (pin "72") (pinfunction "72_72") (pintype "bidirectional"))
    )
    (net (code "131") (name "B34_L19_N") (class "Default")
      (node (ref "JM1") (pin "71") (pinfunction "71_71") (pintype "bidirectional"))
    )
    (net (code "132") (name "B34_L19_P") (class "Default")
      (node (ref "JM1") (pin "73") (pinfunction "73_73") (pintype "bidirectional"))
    )
    (net (code "133") (name "B34_L20_N") (class "Default")
      (node (ref "JM1") (pin "76") (pinfunction "76_76") (pintype "bidirectional"))
    )
    (net (code "134") (name "B34_L20_P") (class "Default")
      (node (ref "JM1") (pin "78") (pinfunction "78_78") (pintype "bidirectional"))
    )
    (net (code "135") (name "B34_L21_N") (class "Default")
      (node (ref "JM1") (pin "69") (pinfunction "69_69") (pintype "bidirectional"))
    )
    (net (code "136") (name "B34_L21_P") (class "Default")
      (node (ref "JM1") (pin "67") (pinfunction "67_67") (pintype "bidirectional"))
    )
    (net (code "137") (name "B34_L22_N") (class "Default")
      (node (ref "JM1") (pin "75") (pinfunction "75_75") (pintype "bidirectional"))
    )
    (net (code "138") (name "B34_L22_P") (class "Default")
      (node (ref "JM1") (pin "77") (pinfunction "77_77") (pintype "bidirectional"))
    )
    (net (code "139") (name "B34_L23_N") (class "Default")
      (node (ref "JM1") (pin "79") (pinfunction "79_79") (pintype "bidirectional"))
    )
    (net (code "140") (name "B34_L23_P") (class "Default")
      (node (ref "JM1") (pin "81") (pinfunction "81_81") (pintype "bidirectional"))
    )
    (net (code "141") (name "B34_L24_N") (class "Default")
      (node (ref "JM1") (pin "80") (pinfunction "80_80") (pintype "bidirectional"))
    )
    (net (code "142") (name "B34_L24_P") (class "Default")
      (node (ref "JM1") (pin "82") (pinfunction "82_82") (pintype "bidirectional"))
    )
    (net (code "143") (name "BOOTMODE") (class "Default")
      (node (ref "JM2") (pin "100") (pinfunction "100_100") (pintype "bidirectional"))
    )
    (net (code "144") (name "DONE") (class "Default")
      (node (ref "D5") (pin "A") (pinfunction "A_A") (pintype "passive"))
      (node (ref "JM1") (pin "96") (pinfunction "96_96") (pintype "bidirectional"))
      (node (ref "R4") (pin "1") (pinfunction "1_1") (pintype "passive"))
    )
    (net (code "145") (name "EN_A") (class "Default")
      (node (ref "R18") (pin "1") (pinfunction "1_1") (pintype "passive"))
      (node (ref "U6") (pin "1") (pinfunction "EN_1") (pintype "input"))
    )
    (net (code "146") (name "EN_B") (class "Default")
      (node (ref "R21") (pin "1") (pinfunction "1_1") (pintype "passive"))
      (node (ref "U7") (pin "1") (pinfunction "EN_1") (pintype "input"))
    )
    (net (code "147") (name "GND") (class "Default")
      (node (ref "C1") (pin "2") (pinfunction "2_2") (pintype "passive"))
      (node (ref "C4") (pin "2") (pinfunction "2_2") (pintype "passive"))
      (node (ref "C56") (pin "2") (pinfunction "2_2") (pintype "passive"))
      (node (ref "C57") (pin "2") (pinfunction "2_2") (pintype "passive"))
      (node (ref "C58") (pin "2") (pinfunction "2_2") (pintype "passive"))
      (node (ref "C59") (pin "2") (pinfunction "2_2") (pintype "passive"))
      (node (ref "D5") (pin "C") (pinfunction "C_C") (pintype "passive"))
      (node (ref "JM1") (pin "100") (pinfunction "100_100") (pintype "bidirectional"))
      (node (ref "JM1") (pin "11") (pinfunction "11_11") (pintype "bidirectional"))
      (node (ref "JM1") (pin "12") (pinfunction "12_12") (pintype "bidirectional"))
      (node (ref "JM1") (pin "17") (pinfunction "17_17") (pintype "bidirectional"))
      (node (ref "JM1") (pin "18") (pinfunction "18_18") (pintype "bidirectional"))
      (node (ref "JM1") (pin "23") (pinfunction "23_23") (pintype "bidirectional"))
      (node (ref "JM1") (pin "24") (pinfunction "24_24") (pintype "bidirectional"))
      (node (ref "JM1") (pin "29") (pinfunction "29_29") (pintype "bidirectional"))
      (node (ref "JM1") (pin "30") (pinfunction "30_30") (pintype "bidirectional"))
      (node (ref "JM1") (pin "47") (pinfunction "47_47") (pintype "bidirectional"))
      (node (ref "JM1") (pin "48") (pinfunction "48_48") (pintype "bidirectional"))
      (node (ref "JM1") (pin "5") (pinfunction "5_5") (pintype "bidirectional"))
      (node (ref "JM1") (pin "6") (pinfunction "6_6") (pintype "bidirectional"))
      (node (ref "JM1") (pin "66") (pinfunction "66_66") (pintype "bidirectional"))
      (node (ref "JM1") (pin "84") (pinfunction "84_84") (pintype "bidirectional"))
      (node (ref "JM1") (pin "98") (pinfunction "98_98") (pintype "bidirectional"))
      (node (ref "JM1") (pin "F1") (pinfunction "F1_F1") (pintype "bidirectional"))
      (node (ref "JM1") (pin "F2") (pinfunction "F2_F2") (pintype "bidirectional"))
      (node (ref "JM2") (pin "17") (pinfunction "17_17") (pintype "bidirectional"))
      (node (ref "JM2") (pin "35") (pinfunction "35_35") (pintype "bidirectional"))
      (node (ref "JM2") (pin "36") (pinfunction "36_36") (pintype "bidirectional"))
      (node (ref "JM2") (pin "72") (pinfunction "72_72") (pintype "bidirectional"))
      (node (ref "JM2") (pin "83") (pinfunction "83_83") (pintype "bidirectional"))
      (node (ref "JM2") (pin "90") (pinfunction "90_90") (pintype "bidirectional"))
      (node (ref "JM2") (pin "F1") (pinfunction "F1_F1") (pintype "bidirectional"))
      (node (ref "JM2") (pin "F2") (pinfunction "F2_F2") (pintype "bidirectional"))
      (node (ref "JP1") (pin "3") (pinfunction "3_3") (pintype "passive"))
      (node (ref "JTAG") (pin "1") (pinfunction "1_1") (pintype "passive"))
      (node (ref "JTAG") (pin "11") (pinfunction "11_11") (pintype "passive"))
      (node (ref "JTAG") (pin "13") (pinfunction "13_13") (pintype "passive"))
      (node (ref "JTAG") (pin "3") (pinfunction "3_3") (pintype "passive"))
      (node (ref "JTAG") (pin "5") (pinfunction "5_5") (pintype "passive"))
      (node (ref "JTAG") (pin "7") (pinfunction "7_7") (pintype "passive"))
      (node (ref "JTAG") (pin "9") (pinfunction "9_9") (pintype "passive"))
      (node (ref "PCIE-NORTH") (pin "A1") (pinfunction "GND_A1") (pintype "passive"))
      (node (ref "PCIE-NORTH") (pin "A10") (pinfunction "GND_A10") (pintype "passive"))
      (node (ref "PCIE-NORTH") (pin "A12") (pinfunction "GND_A12") (pintype "passive"))
      (node (ref "PCIE-NORTH") (pin "A15") (pinfunction "GND_A15") (pintype "passive"))
      (node (ref "PCIE-NORTH") (pin "A18") (pinfunction "GND_A18") (pintype "passive"))
      (node (ref "PCIE-NORTH") (pin "A4") (pinfunction "GND_A4") (pintype "passive"))
      (node (ref "PCIE-NORTH") (pin "A7") (pinfunction "GND_A7") (pintype "passive"))
      (node (ref "PCIE-NORTH") (pin "B15") (pinfunction "GND_B15") (pintype "passive"))
      (node (ref "PCIE-NORTH") (pin "B18") (pinfunction "GND_B18") (pintype "passive"))
      (node (ref "PCIE-SOUTH") (pin "A1") (pinfunction "GND_A1") (pintype "passive"))
      (node (ref "PCIE-SOUTH") (pin "A10") (pinfunction "GND_A10") (pintype "passive"))
      (node (ref "PCIE-SOUTH") (pin "A12") (pinfunction "GND_A12") (pintype "passive"))
      (node (ref "PCIE-SOUTH") (pin "A15") (pinfunction "GND_A15") (pintype "passive"))
      (node (ref "PCIE-SOUTH") (pin "A18") (pinfunction "GND_A18") (pintype "passive"))
      (node (ref "PCIE-SOUTH") (pin "A4") (pinfunction "GND_A4") (pintype "passive"))
      (node (ref "PCIE-SOUTH") (pin "A7") (pinfunction "GND_A7") (pintype "passive"))
      (node (ref "PCIE-SOUTH") (pin "B15") (pinfunction "GND_B15") (pintype "passive"))
      (node (ref "PCIE-SOUTH") (pin "B18") (pinfunction "GND_B18") (pintype "passive"))
      (node (ref "R19") (pin "1") (pinfunction "1_1") (pintype "passive"))
      (node (ref "R22") (pin "1") (pinfunction "1_1") (pintype "passive"))
      (node (ref "R3") (pin "2") (pinfunction "2_2") (pintype "passive"))
      (node (ref "SATA0") (pin "1") (pinfunction "GND_1") (pintype "power_in"))
      (node (ref "SATA0") (pin "4") (pinfunction "GND_4") (pintype "power_in"))
      (node (ref "SATA0") (pin "7") (pinfunction "GND_7") (pintype "power_in"))
      (node (ref "SATA1") (pin "1") (pinfunction "GND_1") (pintype "power_in"))
      (node (ref "SATA1") (pin "4") (pinfunction "GND_4") (pintype "power_in"))
      (node (ref "SATA1") (pin "7") (pinfunction "GND_7") (pintype "power_in"))
      (node (ref "SATA2") (pin "1") (pinfunction "GND_1") (pintype "power_in"))
      (node (ref "SATA2") (pin "4") (pinfunction "GND_4") (pintype "power_in"))
      (node (ref "SATA2") (pin "7") (pinfunction "GND_7") (pintype "power_in"))
      (node (ref "SATA3") (pin "1") (pinfunction "GND_1") (pintype "power_in"))
      (node (ref "SATA3") (pin "4") (pinfunction "GND_4") (pintype "power_in"))
      (node (ref "SATA3") (pin "7") (pinfunction "GND_7") (pintype "power_in"))
      (node (ref "U1") (pin "3") (pinfunction "GND_3") (pintype "passive"))
      (node (ref "U2") (pin "1") (pinfunction "A0_1") (pintype "input"))
      (node (ref "U2") (pin "2") (pinfunction "A1_2") (pintype "input"))
      (node (ref "U2") (pin "3") (pinfunction "A2_3") (pintype "input"))
      (node (ref "U2") (pin "4") (pinfunction "GND_4") (pintype "passive"))
      (node (ref "U2") (pin "EP") (pinfunction "EP_EP") (pintype "passive"))
      (node (ref "U6") (pin "5") (pinfunction "GND_5") (pintype "passive"))
      (node (ref "U6") (pin "6") (pinfunction "GND_6") (pintype "passive"))
      (node (ref "U6") (pin "EP") (pinfunction "GND_EP") (pintype "passive"))
      (node (ref "U7") (pin "5") (pinfunction "GND_5") (pintype "passive"))
      (node (ref "U7") (pin "6") (pinfunction "GND_6") (pintype "passive"))
      (node (ref "U7") (pin "EP") (pinfunction "GND_EP") (pintype "passive"))
    )
    (net (code "148") (name "I2C_V") (class "Default")
      (node (ref "C4") (pin "1") (pinfunction "1_1") (pintype "passive"))
      (node (ref "PCIE-NORTH") (pin "B3") (pinfunction "V_I2C_B3") (pintype "passive"))
      (node (ref "R2") (pin "1") (pinfunction "1_1") (pintype "passive"))
      (node (ref "U2") (pin "8") (pinfunction "VCC_8") (pintype "power_in"))
    )
    (net (code "149") (name "MGT_CLK0_N") (class "Default")
      (node (ref "C3") (pin "2") (pinfunction "2_2") (pintype "passive"))
      (node (ref "JM1") (pin "4") (pinfunction "4_4") (pintype "bidirectional"))
    )
    (net (code "150") (name "MGT_CLK0_P") (class "Default")
      (node (ref "C2") (pin "2") (pinfunction "2_2") (pintype "passive"))
      (node (ref "JM1") (pin "2") (pinfunction "2_2") (pintype "bidirectional"))
    )
    (net (code "151") (name "MGT_RX0_N") (class "Default")
      (node (ref "JM1") (pin "21") (pinfunction "21_21") (pintype "bidirectional"))
      (node (ref "SATA3") (pin "5") (pinfunction "~{B}_5") (pintype "bidirectional"))
    )
    (net (code "152") (name "MGT_RX0_P") (class "Default")
      (node (ref "JM1") (pin "19") (pinfunction "19_19") (pintype "bidirectional"))
      (node (ref "SATA3") (pin "6") (pinfunction "B_6") (pintype "bidirectional"))
    )
    (net (code "153") (name "MGT_RX1_N") (class "Default")
      (node (ref "JM1") (pin "15") (pinfunction "15_15") (pintype "bidirectional"))
      (node (ref "SATA2") (pin "5") (pinfunction "~{B}_5") (pintype "bidirectional"))
    )
    (net (code "154") (name "MGT_RX1_P") (class "Default")
      (node (ref "JM1") (pin "13") (pinfunction "13_13") (pintype "bidirectional"))
      (node (ref "SATA2") (pin "6") (pinfunction "B_6") (pintype "bidirectional"))
    )
    (net (code "155") (name "MGT_RX2_N") (class "Default")
      (node (ref "JM1") (pin "9") (pinfunction "9_9") (pintype "bidirectional"))
      (node (ref "SATA1") (pin "5") (pinfunction "~{B}_5") (pintype "bidirectional"))
    )
    (net (code "156") (name "MGT_RX2_P") (class "Default")
      (node (ref "JM1") (pin "7") (pinfunction "7_7") (pintype "bidirectional"))
      (node (ref "SATA1") (pin "6") (pinfunction "B_6") (pintype "bidirectional"))
    )
    (net (code "157") (name "MGT_RX3_N") (class "Default")
      (node (ref "JM1") (pin "3") (pinfunction "3_3") (pintype "bidirectional"))
      (node (ref "SATA0") (pin "5") (pinfunction "~{B}_5") (pintype "bidirectional"))
    )
    (net (code "158") (name "MGT_RX3_P") (class "Default")
      (node (ref "JM1") (pin "1") (pinfunction "1_1") (pintype "bidirectional"))
      (node (ref "SATA0") (pin "6") (pinfunction "B_6") (pintype "bidirectional"))
    )
    (net (code "159") (name "MGT_TX0_N") (class "Default")
      (node (ref "JM1") (pin "28") (pinfunction "28_28") (pintype "bidirectional"))
      (node (ref "SATA3") (pin "3") (pinfunction "~{A}_3") (pintype "bidirectional"))
    )
    (net (code "160") (name "MGT_TX0_P") (class "Default")
      (node (ref "JM1") (pin "26") (pinfunction "26_26") (pintype "bidirectional"))
      (node (ref "SATA3") (pin "2") (pinfunction "A_2") (pintype "bidirectional"))
    )
    (net (code "161") (name "MGT_TX1_N") (class "Default")
      (node (ref "JM1") (pin "22") (pinfunction "22_22") (pintype "bidirectional"))
      (node (ref "SATA2") (pin "3") (pinfunction "~{A}_3") (pintype "bidirectional"))
    )
    (net (code "162") (name "MGT_TX1_P") (class "Default")
      (node (ref "JM1") (pin "20") (pinfunction "20_20") (pintype "bidirectional"))
      (node (ref "SATA2") (pin "2") (pinfunction "A_2") (pintype "bidirectional"))
    )
    (net (code "163") (name "MGT_TX2_N") (class "Default")
      (node (ref "JM1") (pin "16") (pinfunction "16_16") (pintype "bidirectional"))
      (node (ref "SATA1") (pin "3") (pinfunction "~{A}_3") (pintype "bidirectional"))
    )
    (net (code "164") (name "MGT_TX2_P") (class "Default")
      (node (ref "JM1") (pin "14") (pinfunction "14_14") (pintype "bidirectional"))
      (node (ref "SATA1") (pin "2") (pinfunction "A_2") (pintype "bidirectional"))
    )
    (net (code "165") (name "MGT_TX3_N") (class "Default")
      (node (ref "JM1") (pin "10") (pinfunction "10_10") (pintype "bidirectional"))
      (node (ref "SATA0") (pin "3") (pinfunction "~{A}_3") (pintype "bidirectional"))
    )
    (net (code "166") (name "MGT_TX3_P") (class "Default")
      (node (ref "JM1") (pin "8") (pinfunction "8_8") (pintype "bidirectional"))
      (node (ref "SATA0") (pin "2") (pinfunction "A_2") (pintype "bidirectional"))
    )
    (net (code "167") (name "M_1V8") (class "Default")
      (node (ref "JM2") (pin "18") (pinfunction "18_18") (pintype "bidirectional"))
    )
    (net (code "168") (name "N_5V") (class "Default")
      (node (ref "PCIE-NORTH") (pin "B12") (pinfunction "5V_B12") (pintype "passive"))
    )
    (net (code "169") (name "N_IO0") (class "Default")
      (node (ref "PCIE-NORTH") (pin "B4") (pinfunction "IO0_B4") (pintype "passive"))
    )
    (net (code "170") (name "N_IO1") (class "Default")
      (node (ref "PCIE-NORTH") (pin "B5") (pinfunction "IO1_B5") (pintype "passive"))
    )
    (net (code "171") (name "N_IO2") (class "Default")
      (node (ref "PCIE-NORTH") (pin "B6") (pinfunction "IO2_B6") (pintype "passive"))
    )
    (net (code "172") (name "N_IO3") (class "Default")
      (node (ref "PCIE-NORTH") (pin "B7") (pinfunction "IO3_B7") (pintype "passive"))
    )
    (net (code "173") (name "N_IO4") (class "Default")
      (node (ref "PCIE-NORTH") (pin "B8") (pinfunction "IO4_B8") (pintype "passive"))
    )
    (net (code "174") (name "N_IO5") (class "Default")
      (node (ref "PCIE-NORTH") (pin "B9") (pinfunction "IO5_B9") (pintype "passive"))
    )
    (net (code "175") (name "N_IO6") (class "Default")
      (node (ref "PCIE-NORTH") (pin "B10") (pinfunction "IO6_B10") (pintype "passive"))
    )
    (net (code "176") (name "N_IO7") (class "Default")
      (node (ref "PCIE-NORTH") (pin "B11") (pinfunction "IO7_B11") (pintype "passive"))
    )
    (net (code "177") (name "N_PCIE_V") (class "Default")
      (node (ref "PCIE-NORTH") (pin "B13") (pinfunction "VCC_B13") (pintype "passive"))
    )
    (net (code "178") (name "N_VCCIO") (class "Default")
      (node (ref "PCIE-NORTH") (pin "B14") (pinfunction "VCCIO_B14") (pintype "passive"))
    )
    (net (code "179") (name "Net-(D1-PadC)") (class "Default")
      (node (ref "D1") (pin "C") (pinfunction "C_C") (pintype "passive"))
      (node (ref "R6") (pin "2") (pinfunction "2_2") (pintype "passive"))
    )
    (net (code "180") (name "Net-(D2-PadC)") (class "Default")
      (node (ref "D2") (pin "C") (pinfunction "C_C") (pintype "passive"))
      (node (ref "R7") (pin "2") (pinfunction "2_2") (pintype "passive"))
    )
    (net (code "181") (name "Net-(D3-PadC)") (class "Default")
      (node (ref "D3") (pin "C") (pinfunction "C_C") (pintype "passive"))
      (node (ref "R8") (pin "2") (pinfunction "2_2") (pintype "passive"))
    )
    (net (code "182") (name "Net-(D4-PadC)") (class "Default")
      (node (ref "D4") (pin "C") (pinfunction "C_C") (pintype "passive"))
      (node (ref "R9") (pin "2") (pinfunction "2_2") (pintype "passive"))
    )
    (net (code "183") (name "Net-(U1-OUT+)") (class "Default")
      (node (ref "C2") (pin "1") (pinfunction "1_1") (pintype "passive"))
      (node (ref "R1") (pin "1") (pinfunction "1_1") (pintype "passive"))
      (node (ref "U1") (pin "4") (pinfunction "OUT+_4") (pintype "output"))
    )
    (net (code "184") (name "Net-(U1-OUT-)") (class "Default")
      (node (ref "C3") (pin "1") (pinfunction "1_1") (pintype "passive"))
      (node (ref "R1") (pin "2") (pinfunction "2_2") (pintype "passive"))
      (node (ref "U1") (pin "5") (pinfunction "OUT-_5") (pintype "output"))
    )
    (net (code "185") (name "Net-(U2-WP)") (class "Default")
      (node (ref "R2") (pin "2") (pinfunction "2_2") (pintype "passive"))
      (node (ref "R3") (pin "1") (pinfunction "1_1") (pintype "passive"))
      (node (ref "U2") (pin "7") (pinfunction "WP_7") (pintype "input"))
    )
    (net (code "186") (name "Net-(U6-FB)") (class "Default")
      (node (ref "R17") (pin "1") (pinfunction "1_1") (pintype "passive"))
      (node (ref "R19") (pin "2") (pinfunction "2_2") (pintype "passive"))
      (node (ref "U6") (pin "7") (pinfunction "FB_7") (pintype "output"))
    )
    (net (code "187") (name "Net-(U7-FB)") (class "Default")
      (node (ref "R20") (pin "1") (pinfunction "1_1") (pintype "passive"))
      (node (ref "R22") (pin "2") (pinfunction "2_2") (pintype "passive"))
      (node (ref "U7") (pin "7") (pinfunction "FB_7") (pintype "output"))
    )
    (net (code "188") (name "PROG_B") (class "Default")
      (node (ref "JM1") (pin "94") (pinfunction "94_94") (pintype "bidirectional"))
    )
    (net (code "189") (name "SCL") (class "Default")
      (node (ref "PCIE-NORTH") (pin "B2") (pinfunction "SCL_B2") (pintype "passive"))
      (node (ref "U2") (pin "6") (pinfunction "SCL_6") (pintype "input"))
    )
    (net (code "190") (name "SDA") (class "Default")
      (node (ref "PCIE-NORTH") (pin "B1") (pinfunction "SDA_B1") (pintype "passive"))
      (node (ref "U2") (pin "5") (pinfunction "SDA_5") (pintype "bidirectional"))
    )
    (net (code "191") (name "SPI-CLK") (class "Default")
      (node (ref "JM2") (pin "67") (pinfunction "67_67") (pintype "bidirectional"))
    )
    (net (code "192") (name "SPI-CS") (class "Default")
      (node (ref "JM2") (pin "69") (pinfunction "69_69") (pintype "bidirectional"))
    )
    (net (code "193") (name "SPI-DQ0") (class "Default")
      (node (ref "JM2") (pin "68") (pinfunction "68_68") (pintype "bidirectional"))
    )
    (net (code "194") (name "SPI-DQ1") (class "Default")
      (node (ref "JM2") (pin "71") (pinfunction "71_71") (pintype "bidirectional"))
    )
    (net (code "195") (name "SPI-DQ2") (class "Default")
      (node (ref "JM2") (pin "73") (pinfunction "73_73") (pintype "bidirectional"))
    )
    (net (code "196") (name "SPI-DQ3") (class "Default")
      (node (ref "JM2") (pin "70") (pinfunction "70_70") (pintype "bidirectional"))
    )
    (net (code "197") (name "S_5V") (class "Default")
      (node (ref "JP1") (pin "1") (pinfunction "1_1") (pintype "passive"))
      (node (ref "PCIE-SOUTH") (pin "B12") (pinfunction "5V_B12") (pintype "passive"))
    )
    (net (code "198") (name "S_PCIE_V") (class "Default")
      (node (ref "PCIE-SOUTH") (pin "B13") (pinfunction "VCC_B13") (pintype "passive"))
    )
    (net (code "199") (name "S_VCCIO") (class "Default")
      (node (ref "JM2") (pin "54") (pinfunction "54_54") (pintype "bidirectional"))
      (node (ref "PCIE-SOUTH") (pin "B14") (pinfunction "VCCIO_B14") (pintype "passive"))
    )
    (net (code "200") (name "TCK") (class "Default")
      (node (ref "JM1") (pin "90") (pinfunction "90_90") (pintype "bidirectional"))
      (node (ref "JTAG") (pin "6") (pinfunction "6_6") (pintype "passive"))
    )
    (net (code "201") (name "TDI") (class "Default")
      (node (ref "JM1") (pin "86") (pinfunction "86_86") (pintype "bidirectional"))
      (node (ref "JTAG") (pin "10") (pinfunction "10_10") (pintype "passive"))
    )
    (net (code "202") (name "TDO") (class "Default")
      (node (ref "JM1") (pin "88") (pinfunction "88_88") (pintype "bidirectional"))
      (node (ref "JTAG") (pin "8") (pinfunction "8_8") (pintype "passive"))
    )
    (net (code "203") (name "TMS") (class "Default")
      (node (ref "JM1") (pin "92") (pinfunction "92_92") (pintype "bidirectional"))
      (node (ref "JTAG") (pin "4") (pinfunction "4_4") (pintype "passive"))
    )
    (net (code "204") (name "VCCIO0") (class "Default")
      (node (ref "JM2") (pin "53") (pinfunction "53_53") (pintype "bidirectional"))
      (node (ref "JTAG") (pin "2") (pinfunction "2_2") (pintype "passive"))
    )
    (net (code "205") (name "VCCIO14") (class "Default")
      (node (ref "JM1") (pin "83") (pinfunction "83_83") (pintype "bidirectional"))
    )
    (net (code "206") (name "VCCIO34") (class "Default")
      (node (ref "JM1") (pin "61") (pinfunction "61_61") (pintype "bidirectional"))
    )
    (net (code "207") (name "VOUT_A") (class "Default")
      (node (ref "C57") (pin "1") (pinfunction "1_1") (pintype "passive"))
      (node (ref "FB11") (pin "1") (pinfunction "1_1") (pintype "passive"))
      (node (ref "R17") (pin "2") (pinfunction "2_2") (pintype "passive"))
      (node (ref "U6") (pin "8") (pinfunction "VOUT_8") (pintype "output"))
    )
    (net (code "208") (name "VOUT_B") (class "Default")
      (node (ref "C59") (pin "1") (pinfunction "1_1") (pintype "passive"))
      (node (ref "FB12") (pin "1") (pinfunction "1_1") (pintype "passive"))
      (node (ref "R20") (pin "2") (pinfunction "2_2") (pintype "passive"))
      (node (ref "U7") (pin "8") (pinfunction "VOUT_8") (pintype "output"))
    )
    (net (code "209") (name "VSUP") (class "Default")
      (node (ref "C56") (pin "1") (pinfunction "1_1") (pintype "passive"))
      (node (ref "C58") (pin "1") (pinfunction "1_1") (pintype "passive"))
      (node (ref "JP1") (pin "2") (pinfunction "2_2") (pintype "passive"))
      (node (ref "R18") (pin "2") (pinfunction "2_2") (pintype "passive"))
      (node (ref "R21") (pin "2") (pinfunction "2_2") (pintype "passive"))
      (node (ref "U6") (pin "3") (pinfunction "VIN_3") (pintype "power_in"))
      (node (ref "U6") (pin "4") (pinfunction "VIN_4") (pintype "power_in"))
      (node (ref "U7") (pin "3") (pinfunction "VIN_3") (pintype "power_in"))
      (node (ref "U7") (pin "4") (pinfunction "VIN_4") (pintype "power_in"))
    )
    (net (code "210") (name "V_CLK") (class "Default")
      (node (ref "C1") (pin "1") (pinfunction "1_1") (pintype "passive"))
      (node (ref "FB1") (pin "2") (pinfunction "2_2") (pintype "passive"))
      (node (ref "U1") (pin "6") (pinfunction "VCC_6") (pintype "power_in"))
    )
    (net (code "211") (name "unconnected-(GPIO-Pad1)") (class "Default")
      (node (ref "GPIO") (pin "1") (pinfunction "1_1") (pintype "passive"))
    )
    (net (code "212") (name "unconnected-(GPIO-Pad2)") (class "Default")
      (node (ref "GPIO") (pin "2") (pinfunction "2_2") (pintype "passive"))
    )
    (net (code "213") (name "unconnected-(GPIO-Pad3)") (class "Default")
      (node (ref "GPIO") (pin "3") (pinfunction "3_3") (pintype "passive"))
    )
    (net (code "214") (name "unconnected-(GPIO-Pad4)") (class "Default")
      (node (ref "GPIO") (pin "4") (pinfunction "4_4") (pintype "passive"))
    )
    (net (code "215") (name "unconnected-(GPIO-Pad5)") (class "Default")
      (node (ref "GPIO") (pin "5") (pinfunction "5_5") (pintype "passive"))
    )
    (net (code "216") (name "unconnected-(JTAG-Pad12)") (class "Default")
      (node (ref "JTAG") (pin "12") (pinfunction "12_12") (pintype "passive"))
    )
    (net (code "217") (name "unconnected-(JTAG-Pad14)") (class "Default")
      (node (ref "JTAG") (pin "14") (pinfunction "14_14") (pintype "passive"))
    )
    (net (code "218") (name "unconnected-(PCIE-NORTH-PWRGD-PadA11)") (class "Default")
      (node (ref "PCIE-NORTH") (pin "A11") (pinfunction "PWRGD_A11") (pintype "passive"))
    )
    (net (code "219") (name "unconnected-(PCIE-SOUTH-PWRGD-PadA11)") (class "Default")
      (node (ref "PCIE-SOUTH") (pin "A11") (pinfunction "PWRGD_A11") (pintype "passive"))
    )
    (net (code "220") (name "unconnected-(PCIE-SOUTH-SCL-PadB2)") (class "Default")
      (node (ref "PCIE-SOUTH") (pin "B2") (pinfunction "SCL_B2") (pintype "passive"))
    )
    (net (code "221") (name "unconnected-(PCIE-SOUTH-SDA-PadB1)") (class "Default")
      (node (ref "PCIE-SOUTH") (pin "B1") (pinfunction "SDA_B1") (pintype "passive"))
    )
    (net (code "222") (name "unconnected-(PCIE-SOUTH-V_I2C-PadB3)") (class "Default")
      (node (ref "PCIE-SOUTH") (pin "B3") (pinfunction "V_I2C_B3") (pintype "passive"))
    )
  )
)
